# OBD2.net
KiCad netlist of a schematic drawn in Altium Designer
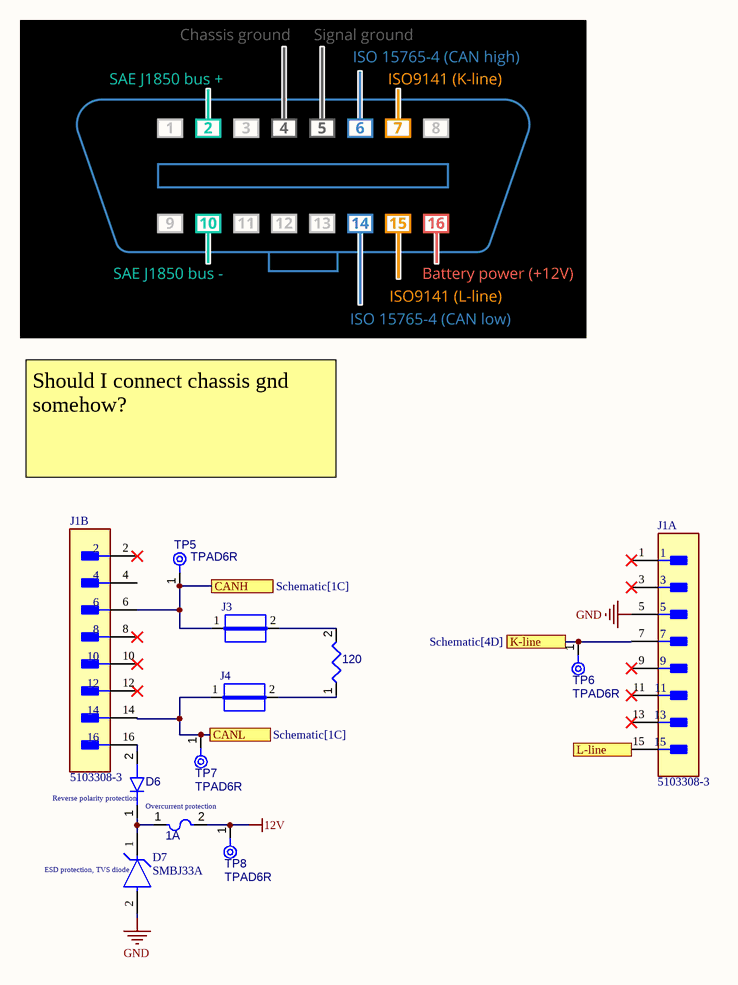
[diagram p0: OBD2.SchDoc]

(export (version "E")
  (design (tool "Eeschema 10.0.6"))
  (components
    (comp (ref "1A")
      (value "Fuses")
      (description "Fuse")
      (libsource (lib "Personal Altium 365 Cloud") (part "FUSE-2"))
    )
    (comp (ref "120")
      (value "Resistors")
      (description "Resistor")
      (libsource (lib "Personal Altium 365 Cloud") (part "RES-2"))
    )
    (comp (ref "D6")
      (value "Diodes")
      (description "Diode")
      (libsource (lib "Personal Altium 365 Cloud") (part "DIODE-2"))
    )
    (comp (ref "D7")
      (value "SMBJ33A")
      (footprint "FP-SMBJ-MFG")
      (description "53.3V Clamp 11.3A Ipp Tvs Diode Surface Mount DO-214AA (SMBJ)")
      (fields (field (name "MANUFACTURER") "Littelfuse Inc"))
      (libsource (lib "Altium Content Vault") (part "f813f71cba58e380607f5dd3caf9714"))
    )
    (comp (ref "J1")
      (value "5103308-3")
      (footprint "FP-5103308-3-MFG")
      (description "CONN HEADER VERT 16POS 2.54MM")
      (libsource (lib "Altium Content Vault") (part "4b6d22b45e2f925f038cba5d936fbcc"))
    )
    (comp (ref "J3")
      (value "JUMPER")
      (footprint "JUMPER")
      (libsource (lib "Personal Altium 365 Cloud") (part "JUMPER"))
    )
    (comp (ref "J4")
      (value "JUMPER")
      (footprint "JUMPER")
      (libsource (lib "Personal Altium 365 Cloud") (part "JUMPER"))
    )
    (comp (ref "TP5")
      (value "TPAD6R")
      (footprint "TP06R")
      (description "0.6mm round")
      (libsource (lib "Personal Altium 365 Cloud") (part "CMP-001-0001-4"))
    )
    (comp (ref "TP6")
      (value "TPAD6R")
      (footprint "TP06R")
      (description "0.6mm round")
      (libsource (lib "Personal Altium 365 Cloud") (part "CMP-001-0001-4"))
    )
    (comp (ref "TP7")
      (value "TPAD6R")
      (footprint "TP06R")
      (description "0.6mm round")
      (libsource (lib "Personal Altium 365 Cloud") (part "CMP-001-0001-4"))
    )
    (comp (ref "TP8")
      (value "TPAD6R")
      (footprint "TP06R")
      (description "0.6mm round")
      (libsource (lib "Personal Altium 365 Cloud") (part "CMP-001-0001-4"))
    )
  )
  (nets
    (net (code "1") (name "/CANH") (class "Default")
      (node (ref "J1") (pin "6") (pinfunction "6_6") (pintype "passive"))
      (node (ref "J3") (pin "1") (pinfunction "1_1") (pintype "passive"))
      (node (ref "TP5") (pin "1") (pinfunction "TP_1") (pintype "passive"))
    )
    (net (code "2") (name "/CANL") (class "Default")
      (node (ref "J1") (pin "14") (pinfunction "14_14") (pintype "passive"))
      (node (ref "J4") (pin "1") (pinfunction "1_1") (pintype "passive"))
      (node (ref "TP7") (pin "1") (pinfunction "TP_1") (pintype "passive"))
    )
    (net (code "3") (name "/K-line") (class "Default")
      (node (ref "J1") (pin "7") (pinfunction "7_7") (pintype "passive"))
      (node (ref "TP6") (pin "1") (pinfunction "TP_1") (pintype "passive"))
    )
    (net (code "4") (name "/L-line") (class "Default")
      (node (ref "J1") (pin "15") (pinfunction "15_15") (pintype "passive"))
    )
    (net (code "5") (name "12V") (class "Default")
      (node (ref "1A") (pin "2") (pinfunction "2_2") (pintype "passive"))
      (node (ref "TP8") (pin "1") (pinfunction "TP_1") (pintype "passive"))
    )
    (net (code "6") (name "GND") (class "Default")
      (node (ref "D7") (pin "2") (pinfunction "A_2") (pintype "passive"))
      (node (ref "J1") (pin "5") (pinfunction "5_5") (pintype "passive"))
    )
    (net (code "7") (name "Net-(120-Pad1)") (class "Default")
      (node (ref "120") (pin "1") (pinfunction "1_1") (pintype "passive"))
      (node (ref "J4") (pin "2") (pinfunction "2_2") (pintype "passive"))
    )
    (net (code "8") (name "Net-(120-Pad2)") (class "Default")
      (node (ref "120") (pin "2") (pinfunction "2_2") (pintype "passive"))
      (node (ref "J3") (pin "2") (pinfunction "2_2") (pintype "passive"))
    )
    (net (code "9") (name "Net-(D6-A)") (class "Default")
      (node (ref "D6") (pin "2") (pinfunction "A_2") (pintype "passive"))
      (node (ref "J1") (pin "16") (pinfunction "16_16") (pintype "passive"))
    )
    (net (code "10") (name "Net-(D6-K)") (class "Default")
      (node (ref "1A") (pin "1") (pinfunction "1_1") (pintype "passive"))
      (node (ref "D6") (pin "1") (pinfunction "K_1") (pintype "passive"))
      (node (ref "D7") (pin "1") (pinfunction "C_1") (pintype "passive"))
    )
    (net (code "11") (name "unconnected-(J1-Pad1)") (class "Default")
      (node (ref "J1") (pin "1") (pinfunction "1_1") (pintype "passive+no_connect"))
    )
    (net (code "12") (name "unconnected-(J1-Pad2)") (class "Default")
      (node (ref "J1") (pin "2") (pinfunction "2_2") (pintype "passive+no_connect"))
    )
    (net (code "13") (name "unconnected-(J1-Pad3)") (class "Default")
      (node (ref "J1") (pin "3") (pinfunction "3_3") (pintype "passive+no_connect"))
    )
    (net (code "14") (name "unconnected-(J1-Pad4)") (class "Default")
      (node (ref "J1") (pin "4") (pinfunction "4_4") (pintype "passive"))
    )
    (net (code "15") (name "unconnected-(J1-Pad8)") (class "Default")
      (node (ref "J1") (pin "8") (pinfunction "8_8") (pintype "passive+no_connect"))
    )
    (net (code "16") (name "unconnected-(J1-Pad9)") (class "Default")
      (node (ref "J1") (pin "9") (pinfunction "9_9") (pintype "passive+no_connect"))
    )
    (net (code "17") (name "unconnected-(J1-Pad10)") (class "Default")
      (node (ref "J1") (pin "10") (pinfunction "10_10") (pintype "passive+no_connect"))
    )
    (net (code "18") (name "unconnected-(J1-Pad11)") (class "Default")
      (node (ref "J1") (pin "11") (pinfunction "11_11") (pintype "passive+no_connect"))
    )
    (net (code "19") (name "unconnected-(J1-Pad12)") (class "Default")
      (node (ref "J1") (pin "12") (pinfunction "12_12") (pintype "passive+no_connect"))
    )
    (net (code "20") (name "unconnected-(J1-Pad13)") (class "Default")
      (node (ref "J1") (pin "13") (pinfunction "13_13") (pintype "passive+no_connect"))
    )
  )
)
